# TeleinfoMySensorsRFM.net
KiCad netlist of a schematic drawn in EAGLE
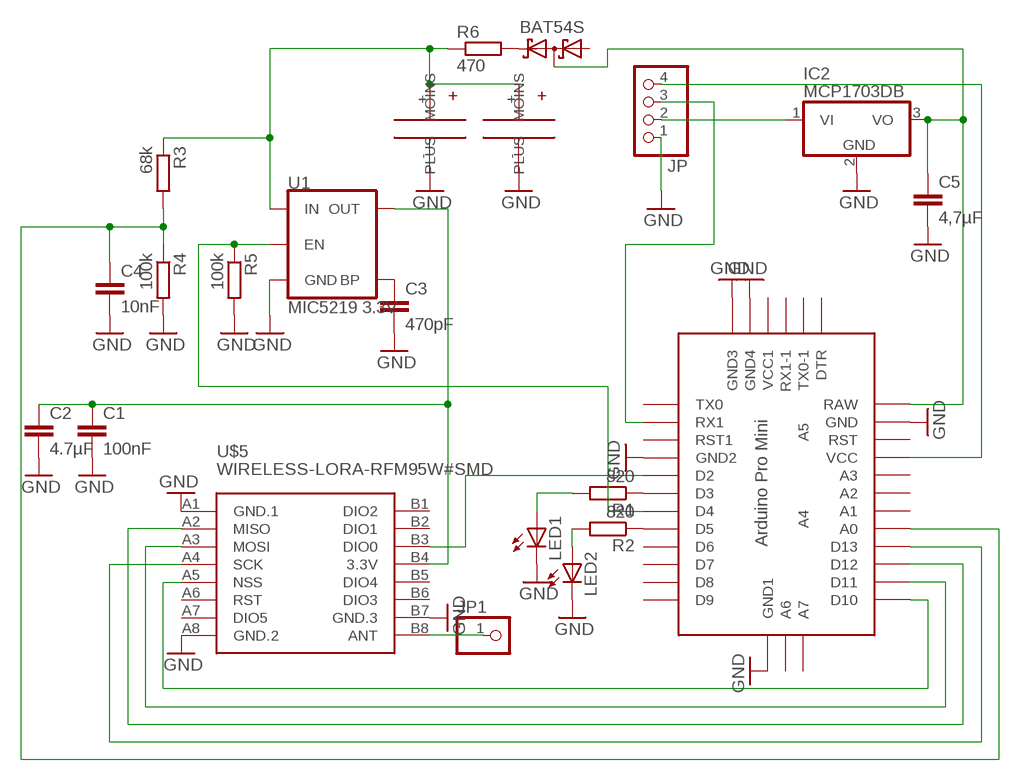
[diagram p0: schematic, sheet 1]

(export (version "E")
  (design (tool "Eeschema 10.0.6"))
  (components
    (comp (ref "C1")
      (value "100nF")
      (footprint "eagle-import:C1206")
      (libsource (lib "eagle-import") (part "C-EUC1206"))
    )
    (comp (ref "C2")
      (value "4.7µF")
      (footprint "eagle-import:C1210")
      (libsource (lib "eagle-import") (part "C-EUC1210"))
    )
    (comp (ref "C3")
      (value "470pF")
      (footprint "eagle-import:C1206")
      (libsource (lib "eagle-import") (part "C-EUC1206"))
    )
    (comp (ref "C4")
      (value "10nF")
      (footprint "eagle-import:C1206")
      (libsource (lib "eagle-import") (part "C-EUC1206"))
    )
    (comp (ref "C5")
      (value "4,7µF")
      (footprint "eagle-import:C1210")
      (libsource (lib "eagle-import") (part "C-EUC1210"))
    )
    (comp (ref "D3")
      (value "BAT54S")
      (footprint "eagle-import:SOT23")
      (libsource (lib "eagle-import") (part "BAT54S"))
    )
    (comp (ref "IC2")
      (value "MCP1703DB")
      (footprint "eagle-import:SOT223")
      (libsource (lib "eagle-import") (part "MCP1703DB"))
    )
    (comp (ref "JP")
      (value "PINHD-1X4")
      (footprint "eagle-import:1X04")
      (libsource (lib "eagle-import") (part "PINHD-1X4"))
    )
    (comp (ref "JP1")
      (value "PINHD-1X1")
      (footprint "eagle-import:1X01")
      (libsource (lib "eagle-import") (part "PINHD-1X1"))
    )
    (comp (ref "LED1")
      (value "LED3MM")
      (footprint "eagle-import:LED3MM")
      (libsource (lib "eagle-import") (part "LED3MM"))
    )
    (comp (ref "LED2")
      (value "LED3MM")
      (footprint "eagle-import:LED3MM")
      (libsource (lib "eagle-import") (part "LED3MM"))
    )
    (comp (ref "R1")
      (value "820")
      (footprint "eagle-import:M1206")
      (libsource (lib "eagle-import") (part "R-EU_M1206"))
    )
    (comp (ref "R2")
      (value "820")
      (footprint "eagle-import:M1206")
      (libsource (lib "eagle-import") (part "R-EU_M1206"))
    )
    (comp (ref "R3")
      (value "68k")
      (footprint "eagle-import:M1206")
      (libsource (lib "eagle-import") (part "R-EU_M1206"))
    )
    (comp (ref "R4")
      (value "100k")
      (footprint "eagle-import:M1206")
      (libsource (lib "eagle-import") (part "R-EU_M1206"))
    )
    (comp (ref "R5")
      (value "100k")
      (footprint "eagle-import:M1206")
      (libsource (lib "eagle-import") (part "R-EU_M1206"))
    )
    (comp (ref "R6")
      (value "470")
      (footprint "eagle-import:M1206")
      (libsource (lib "eagle-import") (part "R-EU_M1206"))
    )
    (comp (ref "U$1")
      (value "ABK-PRO-MINI")
      (footprint "eagle-import:ABK-PRO-MINI")
      (libsource (lib "eagle-import") (part "ABK-PRO-MINI"))
    )
    (comp (ref "U$2")
      (value "SUPERCAPA10")
      (footprint "eagle-import:SUPERCAPA10")
      (libsource (lib "eagle-import") (part "SUPERCAPA10"))
    )
    (comp (ref "U$5")
      (value "WIRELESS-LORA-RFM95W#SMD")
      (footprint "eagle-import:WIRELESS-LORA-RFM95W#SMD")
      (libsource (lib "eagle-import") (part "WIRELESS-LORA-RFM95W#SMD"))
    )
    (comp (ref "U$6")
      (value "SUPERCAPA10")
      (footprint "eagle-import:SUPERCAPA10")
      (libsource (lib "eagle-import") (part "SUPERCAPA10"))
    )
    (comp (ref "U1")
      (value "MIC5219 3.3V")
      (footprint "eagle-import:SOT23-5")
      (libsource (lib "eagle-import") (part "V_REG_MIC52193.3V"))
    )
  )
  (nets
    (net (code "1") (name "GND") (class "Default")
      (node (ref "C1") (pin "2") (pinfunction "2_2") (pintype "passive"))
      (node (ref "C2") (pin "2") (pinfunction "2_2") (pintype "passive"))
      (node (ref "C3") (pin "2") (pinfunction "2_2") (pintype "passive"))
      (node (ref "C4") (pin "2") (pinfunction "2_2") (pintype "passive"))
      (node (ref "C5") (pin "2") (pinfunction "2_2") (pintype "passive"))
      (node (ref "IC2") (pin "2") (pinfunction "GND_2") (pintype "passive"))
      (node (ref "JP") (pin "1") (pinfunction "1_1") (pintype "passive"))
      (node (ref "LED1") (pin "K") (pinfunction "C_K") (pintype "passive"))
      (node (ref "LED2") (pin "K") (pinfunction "C_K") (pintype "passive"))
      (node (ref "R4") (pin "2") (pinfunction "2_2") (pintype "passive"))
      (node (ref "R5") (pin "2") (pinfunction "2_2") (pintype "passive"))
      (node (ref "U$1") (pin "GND") (pinfunction "GND_GND") (pintype "bidirectional"))
      (node (ref "U$1") (pin "GND1") (pinfunction "GND2_GND1") (pintype "bidirectional"))
      (node (ref "U$1") (pin "GND2") (pinfunction "GND3_GND2") (pintype "bidirectional"))
      (node (ref "U$1") (pin "GND3") (pinfunction "GND4_GND3") (pintype "bidirectional"))
      (node (ref "U$1") (pin "GND4") (pinfunction "GND1_GND4") (pintype "bidirectional"))
      (node (ref "U$2") (pin "-") (pinfunction "MOINS_-") (pintype "bidirectional"))
      (node (ref "U$5") (pin "A1") (pinfunction "GND.1_A1") (pintype "power_in"))
      (node (ref "U$5") (pin "A8") (pinfunction "GND.2_A8") (pintype "power_in"))
      (node (ref "U$5") (pin "B7") (pinfunction "GND.3_B7") (pintype "power_in"))
      (node (ref "U$6") (pin "-") (pinfunction "MOINS_-") (pintype "bidirectional"))
      (node (ref "U1") (pin "2") (pinfunction "GND_2") (pintype "input"))
    )
    (net (code "2") (name "Net-(C4-Pad1)") (class "Default")
      (node (ref "C4") (pin "1") (pinfunction "1_1") (pintype "passive"))
      (node (ref "R3") (pin "2") (pinfunction "2_2") (pintype "passive"))
      (node (ref "R4") (pin "1") (pinfunction "1_1") (pintype "passive"))
      (node (ref "U$1") (pin "A0") (pinfunction "A0_A0") (pintype "bidirectional"))
    )
    (net (code "3") (name "Net-(D3-C1A2)") (class "Default")
      (node (ref "C5") (pin "1") (pinfunction "1_1") (pintype "passive"))
      (node (ref "D3") (pin "3") (pinfunction "C1A2_3") (pintype "passive"))
      (node (ref "IC2") (pin "3") (pinfunction "VO_3") (pintype "passive"))
      (node (ref "U$1") (pin "RAW") (pinfunction "RAW_RAW") (pintype "bidirectional"))
    )
    (net (code "4") (name "Net-(D3-C2)") (class "Default")
      (node (ref "D3") (pin "2") (pinfunction "C2_2") (pintype "passive"))
      (node (ref "R6") (pin "2") (pinfunction "2_2") (pintype "passive"))
    )
    (net (code "5") (name "Net-(IC2-VI)") (class "Default")
      (node (ref "IC2") (pin "1") (pinfunction "VI_1") (pintype "input"))
      (node (ref "JP") (pin "2") (pinfunction "2_2") (pintype "passive"))
    )
    (net (code "6") (name "Net-(JP-Pad3)") (class "Default")
      (node (ref "JP") (pin "3") (pinfunction "3_3") (pintype "passive"))
      (node (ref "U$1") (pin "RX1") (pinfunction "RX1_RX1") (pintype "bidirectional"))
    )
    (net (code "7") (name "Net-(JP-Pad4)") (class "Default")
      (node (ref "JP") (pin "4") (pinfunction "4_4") (pintype "passive"))
      (node (ref "U$1") (pin "VCC") (pinfunction "VCC_VCC") (pintype "bidirectional"))
    )
    (net (code "8") (name "Net-(LED1-PadA)") (class "Default")
      (node (ref "LED1") (pin "A") (pinfunction "A_A") (pintype "passive"))
      (node (ref "R1") (pin "2") (pinfunction "2_2") (pintype "passive"))
    )
    (net (code "9") (name "Net-(LED2-PadA)") (class "Default")
      (node (ref "LED2") (pin "A") (pinfunction "A_A") (pintype "passive"))
      (node (ref "R2") (pin "2") (pinfunction "2_2") (pintype "passive"))
    )
    (net (code "10") (name "Net-(R1-Pad1)") (class "Default")
      (node (ref "R1") (pin "1") (pinfunction "1_1") (pintype "passive"))
      (node (ref "U$1") (pin "D3") (pinfunction "D3_D3") (pintype "bidirectional"))
    )
    (net (code "11") (name "Net-(R2-Pad1)") (class "Default")
      (node (ref "R2") (pin "1") (pinfunction "1_1") (pintype "passive"))
      (node (ref "U$1") (pin "D5") (pinfunction "D5_D5") (pintype "bidirectional"))
    )
    (net (code "12") (name "Net-(U$2-PLUS)") (class "Default")
      (node (ref "R3") (pin "1") (pinfunction "1_1") (pintype "passive"))
      (node (ref "R6") (pin "1") (pinfunction "1_1") (pintype "passive"))
      (node (ref "U$2") (pin "+") (pinfunction "PLUS_+") (pintype "bidirectional"))
      (node (ref "U$6") (pin "+") (pinfunction "PLUS_+") (pintype "bidirectional"))
      (node (ref "U1") (pin "1") (pinfunction "IN_1") (pintype "input"))
    )
    (net (code "13") (name "Net-(U$5-3.3V)") (class "Default")
      (node (ref "C1") (pin "1") (pinfunction "1_1") (pintype "passive"))
      (node (ref "C2") (pin "1") (pinfunction "1_1") (pintype "passive"))
      (node (ref "U$5") (pin "B4") (pinfunction "3.3V_B4") (pintype "power_in"))
      (node (ref "U1") (pin "5") (pinfunction "OUT_5") (pintype "passive"))
    )
    (net (code "14") (name "Net-(U$5-ANT)") (class "Default")
      (node (ref "JP1") (pin "1") (pinfunction "1_1") (pintype "passive"))
      (node (ref "U$5") (pin "B8") (pinfunction "ANT_B8") (pintype "passive"))
    )
    (net (code "15") (name "Net-(U$5-DIO0)") (class "Default")
      (node (ref "U$1") (pin "D2") (pinfunction "D2_D2") (pintype "bidirectional"))
      (node (ref "U$5") (pin "B3") (pinfunction "DIO0_B3") (pintype "bidirectional"))
    )
    (net (code "16") (name "Net-(U$5-MISO)") (class "Default")
      (node (ref "U$1") (pin "D12") (pinfunction "D12_D12") (pintype "bidirectional"))
      (node (ref "U$5") (pin "A2") (pinfunction "MISO_A2") (pintype "bidirectional"))
    )
    (net (code "17") (name "Net-(U$5-MOSI)") (class "Default")
      (node (ref "U$1") (pin "D11") (pinfunction "D11_D11") (pintype "bidirectional"))
      (node (ref "U$5") (pin "A3") (pinfunction "MOSI_A3") (pintype "bidirectional"))
    )
    (net (code "18") (name "Net-(U$5-NSS)") (class "Default")
      (node (ref "U$1") (pin "D10") (pinfunction "D10_D10") (pintype "bidirectional"))
      (node (ref "U$5") (pin "A5") (pinfunction "NSS_A5") (pintype "bidirectional"))
    )
    (net (code "19") (name "Net-(U$5-SCK)") (class "Default")
      (node (ref "U$1") (pin "D13") (pinfunction "D13_D13") (pintype "bidirectional"))
      (node (ref "U$5") (pin "A4") (pinfunction "SCK_A4") (pintype "bidirectional"))
    )
    (net (code "20") (name "Net-(U1-BP)") (class "Default")
      (node (ref "C3") (pin "1") (pinfunction "1_1") (pintype "passive"))
      (node (ref "U1") (pin "4") (pinfunction "BP_4") (pintype "input"))
    )
    (net (code "21") (name "Net-(U1-EN)") (class "Default")
      (node (ref "R5") (pin "1") (pinfunction "1_1") (pintype "passive"))
      (node (ref "U$1") (pin "D4") (pinfunction "D4_D4") (pintype "bidirectional"))
      (node (ref "U1") (pin "3") (pinfunction "EN_3") (pintype "input"))
    )
    (net (code "22") (name "unconnected-(D3-A1-Pad1)") (class "Default")
      (node (ref "D3") (pin "1") (pinfunction "A1_1") (pintype "passive"))
    )
    (net (code "23") (name "unconnected-(U$1-PadA1)") (class "Default")
      (node (ref "U$1") (pin "A1") (pinfunction "A1_A1") (pintype "bidirectional"))
    )
    (net (code "24") (name "unconnected-(U$1-PadA2)") (class "Default")
      (node (ref "U$1") (pin "A2") (pinfunction "A2_A2") (pintype "bidirectional"))
    )
    (net (code "25") (name "unconnected-(U$1-PadA3)") (class "Default")
      (node (ref "U$1") (pin "A3") (pinfunction "A3_A3") (pintype "bidirectional"))
    )
    (net (code "26") (name "unconnected-(U$1-PadA4)") (class "Default")
      (node (ref "U$1") (pin "A4") (pinfunction "A4_A4") (pintype "bidirectional"))
    )
    (net (code "27") (name "unconnected-(U$1-PadA5)") (class "Default")
      (node (ref "U$1") (pin "A5") (pinfunction "A5_A5") (pintype "bidirectional"))
    )
    (net (code "28") (name "unconnected-(U$1-PadA6)") (class "Default")
      (node (ref "U$1") (pin "A6") (pinfunction "A6_A6") (pintype "bidirectional"))
    )
    (net (code "29") (name "unconnected-(U$1-PadA7)") (class "Default")
      (node (ref "U$1") (pin "A7") (pinfunction "A7_A7") (pintype "bidirectional"))
    )
    (net (code "30") (name "unconnected-(U$1-PadD6)") (class "Default")
      (node (ref "U$1") (pin "D6") (pinfunction "D6_D6") (pintype "bidirectional"))
    )
    (net (code "31") (name "unconnected-(U$1-PadD7)") (class "Default")
      (node (ref "U$1") (pin "D7") (pinfunction "D7_D7") (pintype "bidirectional"))
    )
    (net (code "32") (name "unconnected-(U$1-PadD8)") (class "Default")
      (node (ref "U$1") (pin "D8") (pinfunction "D8_D8") (pintype "bidirectional"))
    )
    (net (code "33") (name "unconnected-(U$1-PadD9)") (class "Default")
      (node (ref "U$1") (pin "D9") (pinfunction "D9_D9") (pintype "bidirectional"))
    )
    (net (code "34") (name "unconnected-(U$1-PadDTR)") (class "Default")
      (node (ref "U$1") (pin "DTR") (pinfunction "DTR_DTR") (pintype "bidirectional"))
    )
    (net (code "35") (name "unconnected-(U$1-PadRST)") (class "Default")
      (node (ref "U$1") (pin "RST") (pinfunction "RST_RST") (pintype "bidirectional"))
    )
    (net (code "36") (name "unconnected-(U$1-PadRST1)") (class "Default")
      (node (ref "U$1") (pin "RST1") (pinfunction "RST1_RST1") (pintype "bidirectional"))
    )
    (net (code "37") (name "unconnected-(U$1-PadRX1-1)") (class "Default")
      (node (ref "U$1") (pin "RX1-1") (pinfunction "RX1-1_RX1-1") (pintype "bidirectional"))
    )
    (net (code "38") (name "unconnected-(U$1-PadTX0)") (class "Default")
      (node (ref "U$1") (pin "TX0") (pinfunction "TX0_TX0") (pintype "bidirectional"))
    )
    (net (code "39") (name "unconnected-(U$1-PadTX0-1)") (class "Default")
      (node (ref "U$1") (pin "TX0-1") (pinfunction "TX0-1_TX0-1") (pintype "bidirectional"))
    )
    (net (code "40") (name "unconnected-(U$1-PadVCC1)") (class "Default")
      (node (ref "U$1") (pin "VCC1") (pinfunction "VCC1_VCC1") (pintype "bidirectional"))
    )
    (net (code "41") (name "unconnected-(U$5-DIO1-PadB2)") (class "Default")
      (node (ref "U$5") (pin "B2") (pinfunction "DIO1_B2") (pintype "bidirectional"))
    )
    (net (code "42") (name "unconnected-(U$5-DIO2-PadB1)") (class "Default")
      (node (ref "U$5") (pin "B1") (pinfunction "DIO2_B1") (pintype "bidirectional"))
    )
    (net (code "43") (name "unconnected-(U$5-DIO3-PadB6)") (class "Default")
      (node (ref "U$5") (pin "B6") (pinfunction "DIO3_B6") (pintype "bidirectional"))
    )
    (net (code "44") (name "unconnected-(U$5-DIO4-PadB5)") (class "Default")
      (node (ref "U$5") (pin "B5") (pinfunction "DIO4_B5") (pintype "bidirectional"))
    )
    (net (code "45") (name "unconnected-(U$5-DIO5-PadA7)") (class "Default")
      (node (ref "U$5") (pin "A7") (pinfunction "DIO5_A7") (pintype "bidirectional"))
    )
    (net (code "46") (name "unconnected-(U$5-RST-PadA6)") (class "Default")
      (node (ref "U$5") (pin "A6") (pinfunction "RST_A6") (pintype "bidirectional"))
    )
  )
)
